# blink1mk3_005t5.net
KiCad netlist of a schematic drawn in EAGLE
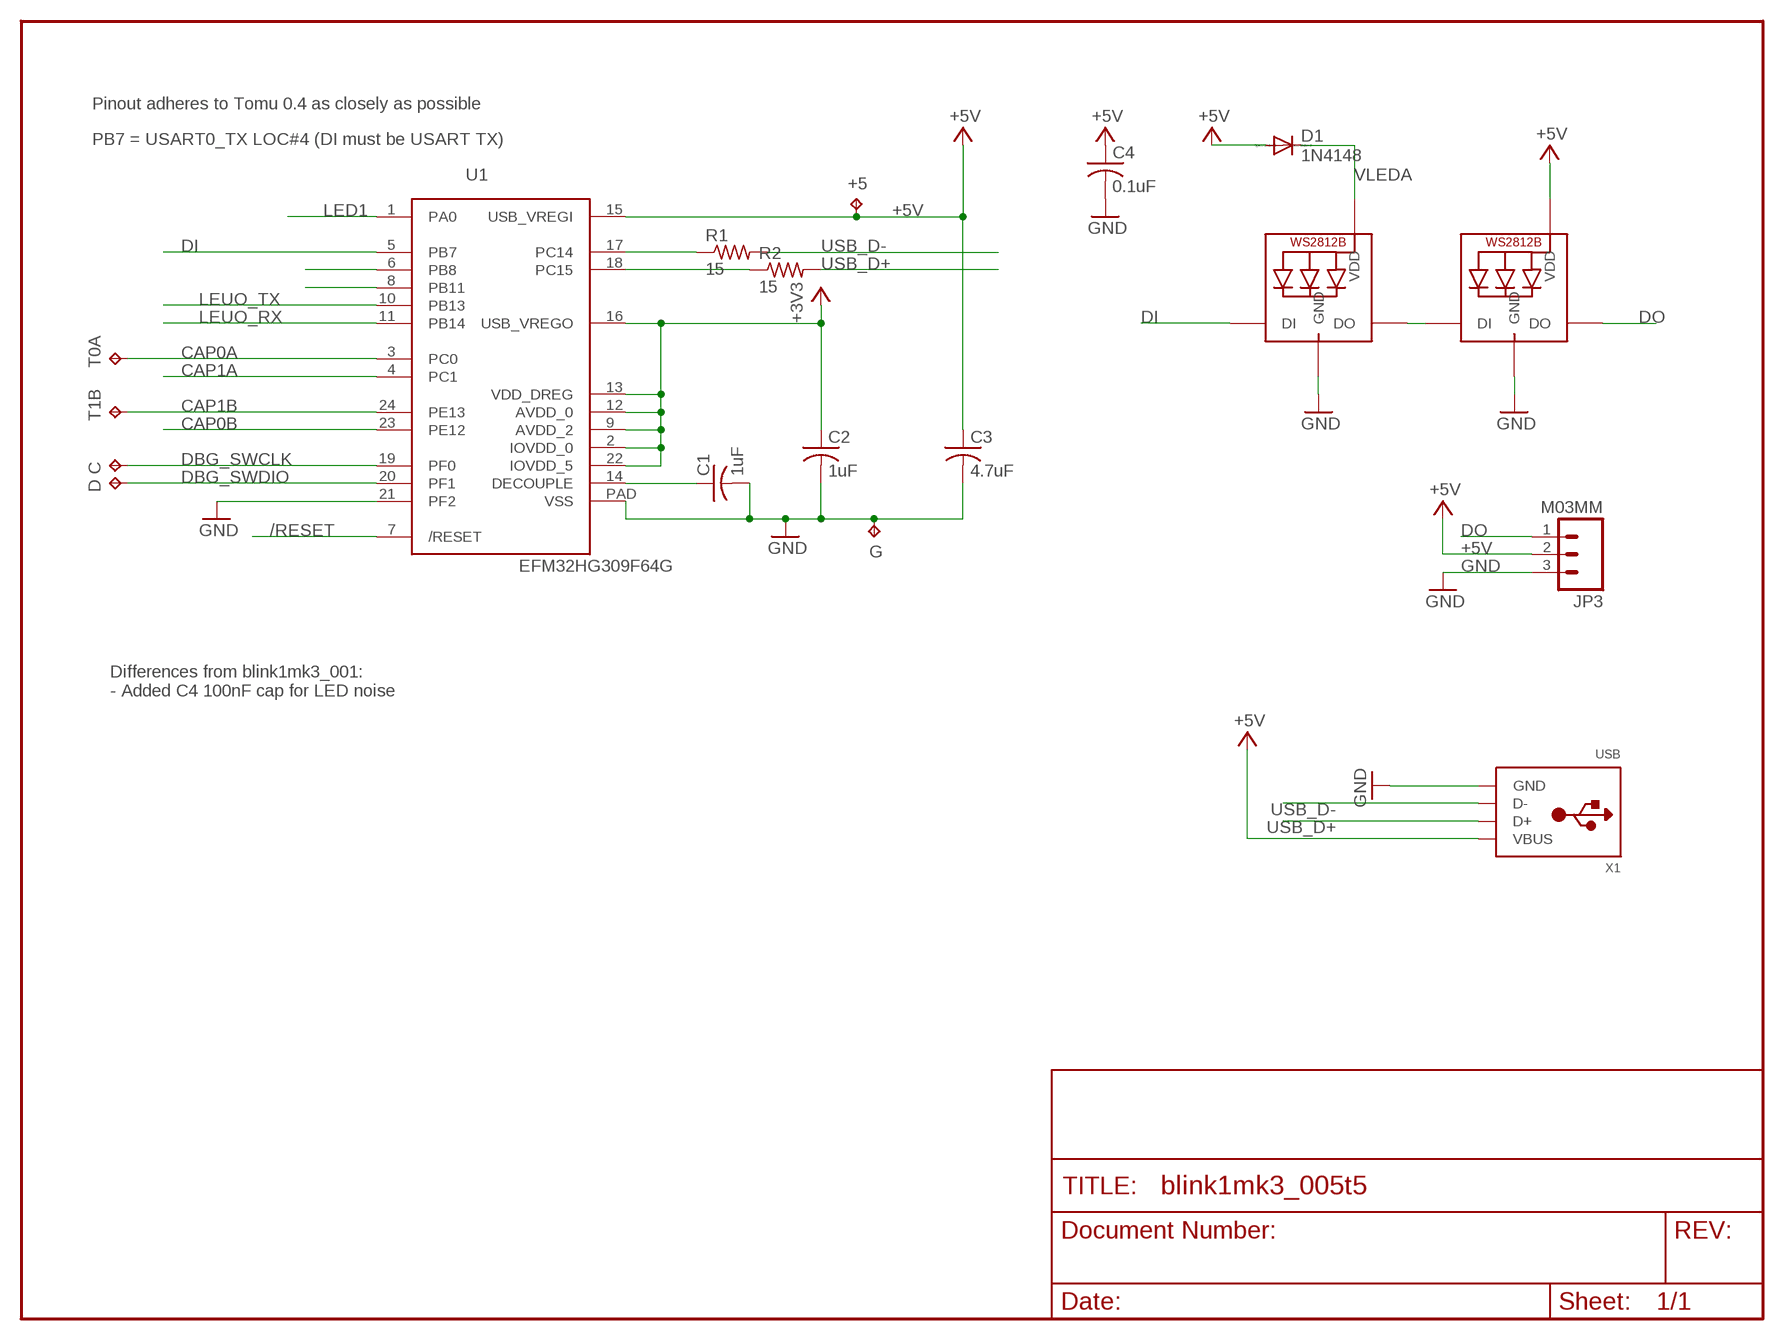
[diagram p0: schematic, sheet 1]

(export (version "E")
  (design (tool "Eeschema 10.0.6"))
  (components
    (comp (ref "+5")
      (value "TPTP10R")
      (footprint "eagle-import:TP10R")
      (libsource (lib "eagle-import") (part "TPTP10R"))
    )
    (comp (ref "C")
      (value "TPTP10R")
      (footprint "eagle-import:TP10R")
      (libsource (lib "eagle-import") (part "TPTP10R"))
    )
    (comp (ref "C1")
      (value "1uF")
      (footprint "eagle-import:C0402")
      (libsource (lib "eagle-import") (part "C-USC0402"))
    )
    (comp (ref "C2")
      (value "1uF")
      (footprint "eagle-import:C0402")
      (libsource (lib "eagle-import") (part "C-USC0402"))
    )
    (comp (ref "C3")
      (value "4.7uF")
      (footprint "eagle-import:C0402")
      (libsource (lib "eagle-import") (part "C-USC0402"))
    )
    (comp (ref "C4")
      (value "0.1uF")
      (footprint "eagle-import:C0402")
      (libsource (lib "eagle-import") (part "C-USC0402"))
    )
    (comp (ref "D")
      (value "TPTP10R")
      (footprint "eagle-import:TP10R")
      (libsource (lib "eagle-import") (part "TPTP10R"))
    )
    (comp (ref "D1")
      (value "1N4148")
      (footprint "eagle-import:SOD523")
      (libsource (lib "eagle-import") (part "DIODE-SOD523"))
    )
    (comp (ref "G")
      (value "TPTP10R")
      (footprint "eagle-import:TP10R")
      (libsource (lib "eagle-import") (part "TPTP10R"))
    )
    (comp (ref "JP3")
      (value "M03MM")
      (footprint "eagle-import:1X03-1.5MM")
      (libsource (lib "eagle-import") (part "M03MM"))
    )
    (comp (ref "LED1")
      (value "SK6812MINI")
      (footprint "eagle-import:LED3535")
      (libsource (lib "eagle-import") (part "WS2812B3535"))
    )
    (comp (ref "LED2")
      (value "SK6812MINI")
      (footprint "eagle-import:LED3535")
      (libsource (lib "eagle-import") (part "WS2812B3535"))
    )
    (comp (ref "R1")
      (value "15")
      (footprint "eagle-import:R0402")
      (libsource (lib "eagle-import") (part "R-US_R0402"))
    )
    (comp (ref "R2")
      (value "15")
      (footprint "eagle-import:R0402")
      (libsource (lib "eagle-import") (part "R-US_R0402"))
    )
    (comp (ref "T0A")
      (value "TPTP15R")
      (footprint "eagle-import:TP15R")
      (libsource (lib "eagle-import") (part "TPTP15R"))
    )
    (comp (ref "T1B")
      (value "TPTP15R")
      (footprint "eagle-import:TP15R")
      (libsource (lib "eagle-import") (part "TPTP15R"))
    )
    (comp (ref "U1")
      (value "EFM32HG309F64G")
      (footprint "eagle-import:QFN24PAD")
      (libsource (lib "eagle-import") (part "EFM32HG309F64G"))
    )
    (comp (ref "X1")
      (value "USB")
      (footprint "eagle-import:MOLEX-48037-1000")
      (libsource (lib "eagle-import") (part "USB"))
    )
  )
  (nets
    (net (code "1") (name "+3V3") (class "Default")
      (node (ref "C2") (pin "1") (pinfunction "1_1") (pintype "passive"))
      (node (ref "U1") (pin "12") (pinfunction "AVDD_0_12") (pintype "bidirectional"))
      (node (ref "U1") (pin "13") (pinfunction "VDD_DREG_13") (pintype "bidirectional"))
      (node (ref "U1") (pin "16") (pinfunction "USB_VREGO_16") (pintype "bidirectional"))
      (node (ref "U1") (pin "2") (pinfunction "IOVDD_0_2") (pintype "bidirectional"))
      (node (ref "U1") (pin "22") (pinfunction "IOVDD_5_22") (pintype "bidirectional"))
      (node (ref "U1") (pin "9") (pinfunction "AVDD_2_9") (pintype "bidirectional"))
    )
    (net (code "2") (name "+5V") (class "Default")
      (node (ref "+5") (pin "TP") (pinfunction "TP_TP") (pintype "input"))
      (node (ref "C3") (pin "1") (pinfunction "1_1") (pintype "passive"))
      (node (ref "C4") (pin "1") (pinfunction "1_1") (pintype "passive"))
      (node (ref "D1") (pin "A") (pinfunction "A_A") (pintype "passive"))
      (node (ref "JP3") (pin "2") (pinfunction "2_2") (pintype "passive"))
      (node (ref "LED2") (pin "2") (pinfunction "VDD_2") (pintype "power_in"))
      (node (ref "U1") (pin "15") (pinfunction "USB_VREGI_15") (pintype "bidirectional"))
      (node (ref "X1") (pin "1") (pinfunction "VBUS_1") (pintype "power_in"))
    )
    (net (code "3") (name "/CAP0A") (class "Default")
      (node (ref "T0A") (pin "TP") (pinfunction "TP_TP") (pintype "input"))
      (node (ref "U1") (pin "3") (pinfunction "PC0_3") (pintype "bidirectional"))
    )
    (net (code "4") (name "/CAP0B") (class "Default")
      (node (ref "U1") (pin "23") (pinfunction "PE12_23") (pintype "bidirectional"))
    )
    (net (code "5") (name "/CAP1A") (class "Default")
      (node (ref "U1") (pin "4") (pinfunction "PC1_4") (pintype "bidirectional"))
    )
    (net (code "6") (name "/CAP1B") (class "Default")
      (node (ref "T1B") (pin "TP") (pinfunction "TP_TP") (pintype "input"))
      (node (ref "U1") (pin "24") (pinfunction "PE13_24") (pintype "bidirectional"))
    )
    (net (code "7") (name "/DBG_SWCLK") (class "Default")
      (node (ref "C") (pin "TP") (pinfunction "TP_TP") (pintype "input"))
      (node (ref "U1") (pin "19") (pinfunction "PF0_19") (pintype "bidirectional"))
    )
    (net (code "8") (name "/DBG_SWDIO") (class "Default")
      (node (ref "D") (pin "TP") (pinfunction "TP_TP") (pintype "input"))
      (node (ref "U1") (pin "20") (pinfunction "PF1_20") (pintype "bidirectional"))
    )
    (net (code "9") (name "/DI") (class "Default")
      (node (ref "LED1") (pin "1") (pinfunction "DI_1") (pintype "input"))
      (node (ref "U1") (pin "5") (pinfunction "PB7_5") (pintype "bidirectional"))
    )
    (net (code "10") (name "/DO") (class "Default")
      (node (ref "JP3") (pin "1") (pinfunction "1_1") (pintype "passive"))
      (node (ref "LED2") (pin "3") (pinfunction "DO_3") (pintype "output"))
    )
    (net (code "11") (name "/LED1") (class "Default")
      (node (ref "U1") (pin "1") (pinfunction "PA0_1") (pintype "bidirectional"))
    )
    (net (code "12") (name "/LEUO_RX") (class "Default")
      (node (ref "U1") (pin "11") (pinfunction "PB14_11") (pintype "bidirectional"))
    )
    (net (code "13") (name "/LEUO_TX") (class "Default")
      (node (ref "U1") (pin "10") (pinfunction "PB13_10") (pintype "bidirectional"))
    )
    (net (code "14") (name "/USB_D+") (class "Default")
      (node (ref "R2") (pin "2") (pinfunction "2_2") (pintype "passive"))
      (node (ref "X1") (pin "3") (pinfunction "D+_3") (pintype "bidirectional"))
    )
    (net (code "15") (name "/USB_D-") (class "Default")
      (node (ref "R1") (pin "2") (pinfunction "2_2") (pintype "passive"))
      (node (ref "X1") (pin "2") (pinfunction "D-_2") (pintype "bidirectional"))
    )
    (net (code "16") (name "/VLEDA") (class "Default")
      (node (ref "D1") (pin "C") (pinfunction "C_C") (pintype "passive"))
      (node (ref "LED1") (pin "2") (pinfunction "VDD_2") (pintype "power_in"))
    )
    (net (code "17") (name "/{slash}RESET") (class "Default")
      (node (ref "U1") (pin "7") (pinfunction "/RESET_7") (pintype "bidirectional"))
    )
    (net (code "18") (name "GND") (class "Default")
      (node (ref "C1") (pin "2") (pinfunction "2_2") (pintype "passive"))
      (node (ref "C2") (pin "2") (pinfunction "2_2") (pintype "passive"))
      (node (ref "C3") (pin "2") (pinfunction "2_2") (pintype "passive"))
      (node (ref "C4") (pin "2") (pinfunction "2_2") (pintype "passive"))
      (node (ref "G") (pin "TP") (pinfunction "TP_TP") (pintype "input"))
      (node (ref "JP3") (pin "3") (pinfunction "3_3") (pintype "passive"))
      (node (ref "LED1") (pin "4") (pinfunction "GND_4") (pintype "power_in"))
      (node (ref "LED2") (pin "4") (pinfunction "GND_4") (pintype "power_in"))
      (node (ref "U1") (pin "21") (pinfunction "PF2_21") (pintype "bidirectional"))
      (node (ref "U1") (pin "PAD") (pinfunction "VSS_PAD") (pintype "bidirectional"))
      (node (ref "X1") (pin "4") (pinfunction "GND_4") (pintype "power_in"))
    )
    (net (code "19") (name "Net-(LED1-DO)") (class "Default")
      (node (ref "LED1") (pin "3") (pinfunction "DO_3") (pintype "output"))
      (node (ref "LED2") (pin "1") (pinfunction "DI_1") (pintype "input"))
    )
    (net (code "20") (name "Net-(U1-DECOUPLE)") (class "Default")
      (node (ref "C1") (pin "1") (pinfunction "1_1") (pintype "passive"))
      (node (ref "U1") (pin "14") (pinfunction "DECOUPLE_14") (pintype "bidirectional"))
    )
    (net (code "21") (name "Net-(U1-PC14)") (class "Default")
      (node (ref "R1") (pin "1") (pinfunction "1_1") (pintype "passive"))
      (node (ref "U1") (pin "17") (pinfunction "PC14_17") (pintype "bidirectional"))
    )
    (net (code "22") (name "Net-(U1-PC15)") (class "Default")
      (node (ref "R2") (pin "1") (pinfunction "1_1") (pintype "passive"))
      (node (ref "U1") (pin "18") (pinfunction "PC15_18") (pintype "bidirectional"))
    )
    (net (code "23") (name "unconnected-(U1-PB8-Pad6)") (class "Default")
      (node (ref "U1") (pin "6") (pinfunction "PB8_6") (pintype "bidirectional"))
    )
    (net (code "24") (name "unconnected-(U1-PB11-Pad8)") (class "Default")
      (node (ref "U1") (pin "8") (pinfunction "PB11_8") (pintype "bidirectional"))
    )
  )
)
